# EAA690_RFID.net
KiCad netlist of a schematic drawn in EAGLE
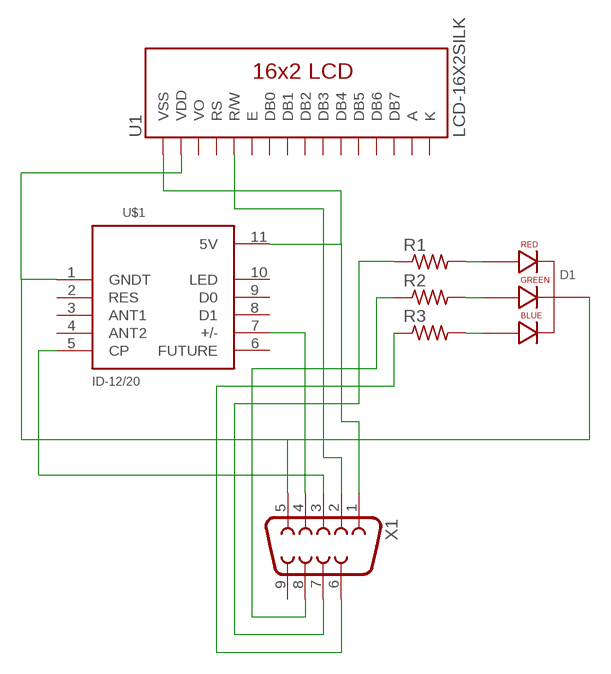
[diagram p0: schematic, sheet 1]

(export (version "E")
  (design (tool "Eeschema 10.0.6"))
  (components
    (comp (ref "D1")
      (value "LED-RGB-CC-THRUDIFFUSE")
      (footprint "eagle-import:LED-RGB-THRU")
      (libsource (lib "eagle-import") (part "LED-RGB-CC-THRUDIFFUSE"))
    )
    (comp (ref "R1")
      (value "R-US_0204/7")
      (footprint "eagle-import:0204_7")
      (libsource (lib "eagle-import") (part "R-US_0204/7"))
    )
    (comp (ref "R2")
      (value "R-US_0204/7")
      (footprint "eagle-import:0204_7")
      (libsource (lib "eagle-import") (part "R-US_0204/7"))
    )
    (comp (ref "R3")
      (value "R-US_0204/7")
      (footprint "eagle-import:0204_7")
      (libsource (lib "eagle-import") (part "R-US_0204/7"))
    )
    (comp (ref "U$1")
      (value "ID-12/20")
      (footprint "eagle-import:ID-12")
      (libsource (lib "eagle-import") (part "ID-12/20"))
    )
    (comp (ref "U1")
      (value "LCD-16X2SILK")
      (footprint "eagle-import:LCD-16X2")
      (libsource (lib "eagle-import") (part "LCD-16X2SILK"))
    )
    (comp (ref "X1")
      (value "DB9FEMALE")
      (footprint "eagle-import:DB9")
      (libsource (lib "eagle-import") (part "DB9FEMALE"))
    )
  )
  (nets
    (net (code "1") (name "/A") (class "Default")
      (node (ref "U1") (pin "15") (pinfunction "A_15") (pintype "power_in"))
    )
    (net (code "2") (name "/K") (class "Default")
      (node (ref "U1") (pin "16") (pinfunction "K_16") (pintype "power_in"))
    )
    (net (code "3") (name "Net-(D1-BLUE_CATHODE)") (class "Default")
      (node (ref "D1") (pin "4") (pinfunction "BLUE_CATHODE_4") (pintype "bidirectional"))
      (node (ref "R3") (pin "2") (pinfunction "2_2") (pintype "passive"))
    )
    (net (code "4") (name "Net-(D1-CATHODE)") (class "Default")
      (node (ref "D1") (pin "2") (pinfunction "CATHODE_2") (pintype "bidirectional"))
      (node (ref "U$1") (pin "1") (pinfunction "GNDT_1") (pintype "bidirectional"))
      (node (ref "U1") (pin "2") (pinfunction "VDD_2") (pintype "power_in"))
      (node (ref "X1") (pin "5") (pinfunction "5_5") (pintype "passive"))
    )
    (net (code "5") (name "Net-(D1-GREEN_CATHODE)") (class "Default")
      (node (ref "D1") (pin "3") (pinfunction "GREEN_CATHODE_3") (pintype "bidirectional"))
      (node (ref "R2") (pin "2") (pinfunction "2_2") (pintype "passive"))
    )
    (net (code "6") (name "Net-(D1-RED_CATHODE)") (class "Default")
      (node (ref "D1") (pin "1") (pinfunction "RED_CATHODE_1") (pintype "bidirectional"))
      (node (ref "R1") (pin "2") (pinfunction "2_2") (pintype "passive"))
    )
    (net (code "7") (name "Net-(R1-Pad1)") (class "Default")
      (node (ref "R1") (pin "1") (pinfunction "1_1") (pintype "passive"))
      (node (ref "X1") (pin "7") (pinfunction "7_7") (pintype "passive"))
    )
    (net (code "8") (name "Net-(R2-Pad1)") (class "Default")
      (node (ref "R2") (pin "1") (pinfunction "1_1") (pintype "passive"))
      (node (ref "X1") (pin "8") (pinfunction "8_8") (pintype "passive"))
    )
    (net (code "9") (name "Net-(R3-Pad1)") (class "Default")
      (node (ref "R3") (pin "1") (pinfunction "1_1") (pintype "passive"))
      (node (ref "X1") (pin "6") (pinfunction "6_6") (pintype "passive"))
    )
    (net (code "10") (name "Net-(U$1-+{slash}-)") (class "Default")
      (node (ref "U$1") (pin "7") (pinfunction "+/-_7") (pintype "bidirectional"))
      (node (ref "X1") (pin "4") (pinfunction "4_4") (pintype "passive"))
    )
    (net (code "11") (name "Net-(U$1-5V)") (class "Default")
      (node (ref "U$1") (pin "11") (pinfunction "5V_11") (pintype "bidirectional"))
      (node (ref "U1") (pin "1") (pinfunction "VSS_1") (pintype "power_in"))
      (node (ref "X1") (pin "1") (pinfunction "1_1") (pintype "passive"))
    )
    (net (code "12") (name "Net-(U$1-CP)") (class "Default")
      (node (ref "U$1") (pin "5") (pinfunction "CP_5") (pintype "bidirectional"))
      (node (ref "X1") (pin "3") (pinfunction "3_3") (pintype "passive"))
    )
    (net (code "13") (name "Net-(U1-R{slash}W)") (class "Default")
      (node (ref "U1") (pin "5") (pinfunction "R/W_5") (pintype "input"))
      (node (ref "X1") (pin "2") (pinfunction "2_2") (pintype "passive"))
    )
    (net (code "14") (name "unconnected-(U$1-ANT1-Pad3)") (class "Default")
      (node (ref "U$1") (pin "3") (pinfunction "ANT1_3") (pintype "bidirectional"))
    )
    (net (code "15") (name "unconnected-(U$1-ANT2-Pad4)") (class "Default")
      (node (ref "U$1") (pin "4") (pinfunction "ANT2_4") (pintype "bidirectional"))
    )
    (net (code "16") (name "unconnected-(U$1-D0-Pad9)") (class "Default")
      (node (ref "U$1") (pin "9") (pinfunction "D0_9") (pintype "bidirectional"))
    )
    (net (code "17") (name "unconnected-(U$1-D1-Pad8)") (class "Default")
      (node (ref "U$1") (pin "8") (pinfunction "D1_8") (pintype "bidirectional"))
    )
    (net (code "18") (name "unconnected-(U$1-FUTURE-Pad6)") (class "Default")
      (node (ref "U$1") (pin "6") (pinfunction "FUTURE_6") (pintype "bidirectional"))
    )
    (net (code "19") (name "unconnected-(U$1-LED-Pad10)") (class "Default")
      (node (ref "U$1") (pin "10") (pinfunction "LED_10") (pintype "bidirectional"))
    )
    (net (code "20") (name "unconnected-(U$1-RES-Pad2)") (class "Default")
      (node (ref "U$1") (pin "2") (pinfunction "RES_2") (pintype "bidirectional"))
    )
    (net (code "21") (name "unconnected-(U1-DB0-Pad7)") (class "Default")
      (node (ref "U1") (pin "7") (pinfunction "DB0_7") (pintype "bidirectional"))
    )
    (net (code "22") (name "unconnected-(U1-DB1-Pad8)") (class "Default")
      (node (ref "U1") (pin "8") (pinfunction "DB1_8") (pintype "bidirectional"))
    )
    (net (code "23") (name "unconnected-(U1-DB2-Pad9)") (class "Default")
      (node (ref "U1") (pin "9") (pinfunction "DB2_9") (pintype "bidirectional"))
    )
    (net (code "24") (name "unconnected-(U1-DB3-Pad10)") (class "Default")
      (node (ref "U1") (pin "10") (pinfunction "DB3_10") (pintype "bidirectional"))
    )
    (net (code "25") (name "unconnected-(U1-DB4-Pad11)") (class "Default")
      (node (ref "U1") (pin "11") (pinfunction "DB4_11") (pintype "bidirectional"))
    )
    (net (code "26") (name "unconnected-(U1-DB5-Pad12)") (class "Default")
      (node (ref "U1") (pin "12") (pinfunction "DB5_12") (pintype "bidirectional"))
    )
    (net (code "27") (name "unconnected-(U1-DB6-Pad13)") (class "Default")
      (node (ref "U1") (pin "13") (pinfunction "DB6_13") (pintype "bidirectional"))
    )
    (net (code "28") (name "unconnected-(U1-DB7-Pad14)") (class "Default")
      (node (ref "U1") (pin "14") (pinfunction "DB7_14") (pintype "bidirectional"))
    )
    (net (code "29") (name "unconnected-(U1-E-Pad6)") (class "Default")
      (node (ref "U1") (pin "6") (pinfunction "E_6") (pintype "input"))
    )
    (net (code "30") (name "unconnected-(U1-RS-Pad4)") (class "Default")
      (node (ref "U1") (pin "4") (pinfunction "RS_4") (pintype "input"))
    )
    (net (code "31") (name "unconnected-(U1-VO-Pad3)") (class "Default")
      (node (ref "U1") (pin "3") (pinfunction "VO_3") (pintype "bidirectional"))
    )
    (net (code "32") (name "unconnected-(X1-Pad9)") (class "Default")
      (node (ref "X1") (pin "9") (pinfunction "9_9") (pintype "passive"))
    )
  )
)
